# ESP8266_SENSOR_Sheet_1.net
KiCad netlist of a schematic drawn in Altium Designer
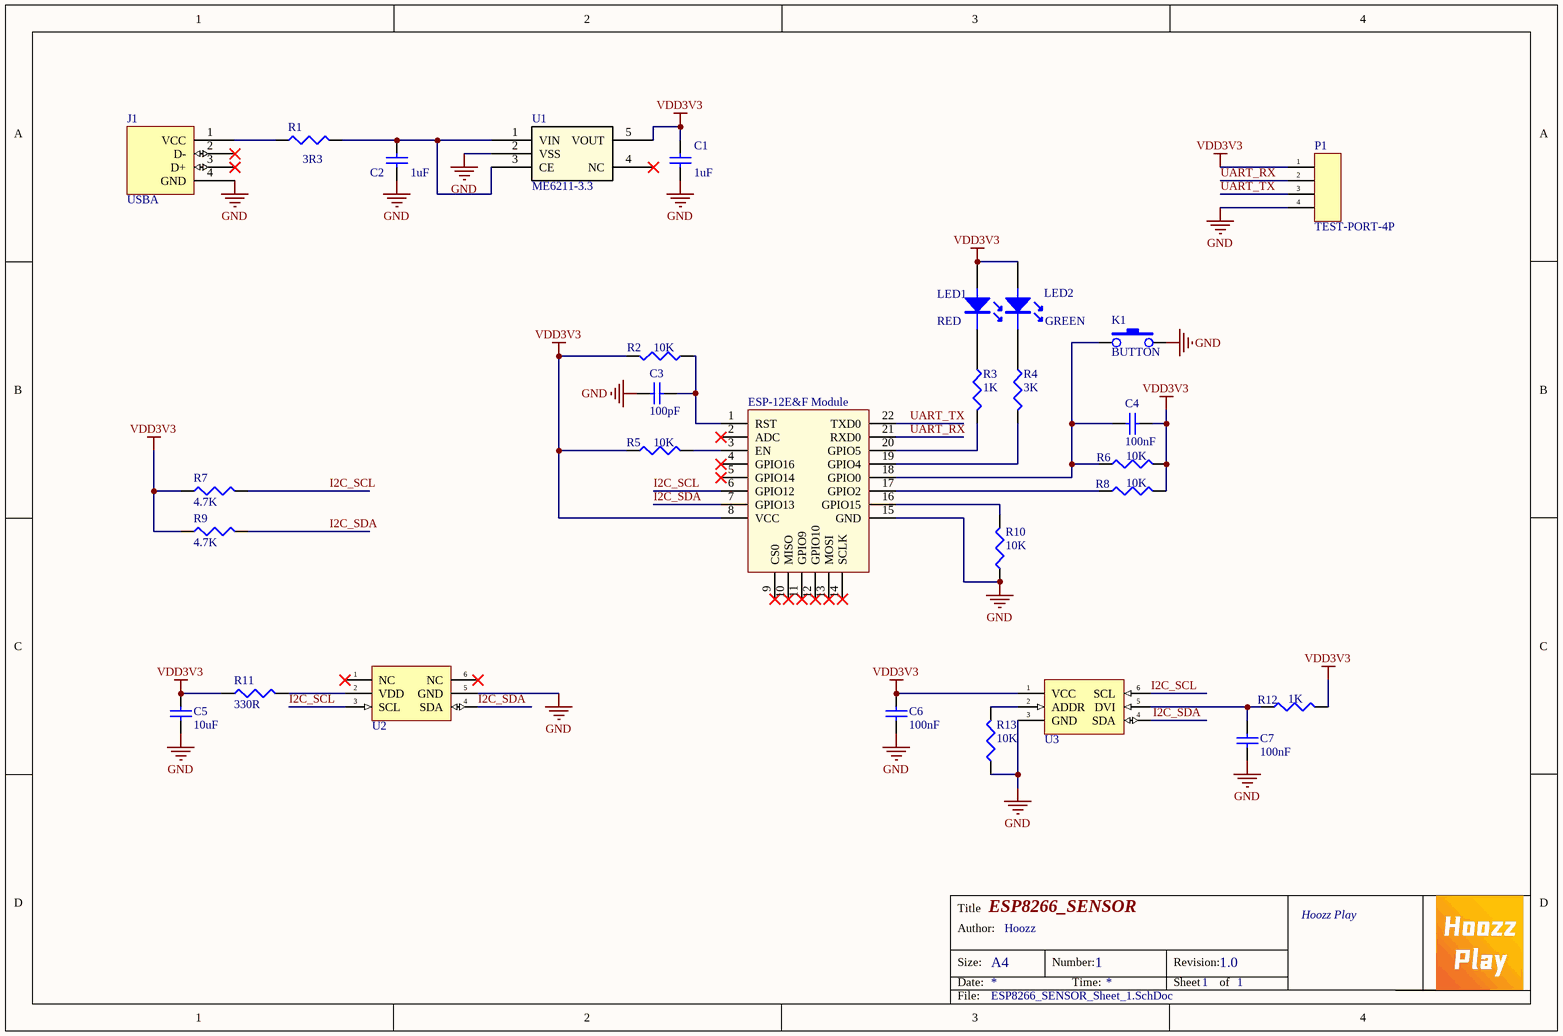
[diagram p0: ESP8266_SENSOR_Sheet_1.SchDoc]

(export (version "E")
  (design (tool "Eeschema 10.0.6"))
  (components
    (comp (ref "C1")
      (value "1uF")
      (footprint "0603")
      (description "Capacitor")
      (fields (field (name "Comment") "Cap") (field (name "PUBLISHER") "Altium Limited"))
      (libsource (lib "CORE_COMPONENT") (part "Cap"))
    )
    (comp (ref "C2")
      (value "1uF")
      (footprint "0603")
      (description "Capacitor")
      (fields (field (name "Comment") "Cap") (field (name "PUBLISHER") "Altium Limited"))
      (libsource (lib "CORE_COMPONENT") (part "Cap"))
    )
    (comp (ref "C3")
      (value "100pF")
      (footprint "0603")
      (description "Capacitor")
      (fields (field (name "Comment") "Cap") (field (name "PUBLISHER") "Altium Limited"))
      (libsource (lib "CORE_COMPONENT") (part "Cap"))
    )
    (comp (ref "C4")
      (value "100nF")
      (footprint "0603")
      (description "Capacitor")
      (fields (field (name "Comment") "Cap") (field (name "PUBLISHER") "Altium Limited"))
      (libsource (lib "CORE_COMPONENT") (part "Cap"))
    )
    (comp (ref "C5")
      (value "10uF")
      (footprint "0603")
      (description "Capacitor")
      (fields (field (name "Comment") "Cap") (field (name "PUBLISHER") "Altium Limited"))
      (libsource (lib "CORE_COMPONENT") (part "Cap"))
    )
    (comp (ref "C6")
      (value "100nF")
      (footprint "0603")
      (description "Capacitor")
      (fields (field (name "Comment") "Cap") (field (name "PUBLISHER") "Altium Limited"))
      (libsource (lib "CORE_COMPONENT") (part "Cap"))
    )
    (comp (ref "C7")
      (value "100nF")
      (footprint "0603")
      (description "Capacitor")
      (fields (field (name "Comment") "Cap") (field (name "PUBLISHER") "Altium Limited"))
      (libsource (lib "CORE_COMPONENT") (part "Cap"))
    )
    (comp (ref "J1")
      (value "USBA")
      (footprint "USB-A-2")
      (description "USB2.0")
      (libsource (lib "CORE_COMPONENT") (part "USBA"))
    )
    (comp (ref "K1") (value "BUTTON") (footprint "BUTTON") (libsource (lib "CORE_COMPONENT") (part "BUTTON")))
    (comp (ref "LED1") (value "RED") (footprint "LED0603") (libsource (lib "CORE_COMPONENT") (part "LED")))
    (comp (ref "LED2") (value "GREEN") (footprint "LED0603") (libsource (lib "CORE_COMPONENT") (part "LED")))
    (comp (ref "M1")
      (value "ESP-12E&F Module")
      (footprint "ESP-12E&F Module")
      (libsource (lib "CORE_COMPONENT") (part "ESP-12E&F Module"))
    )
    (comp (ref "P1")
      (value "TEST-PORT-4P")
      (footprint "TEST_PORT_4P")
      (libsource (lib "CORE_COMPONENT") (part "TEST-PORT-4P"))
    )
    (comp (ref "R1")
      (value "3R3")
      (footprint "0603")
      (description "Resistor")
      (fields (field (name "Comment") "Res") (field (name "PUBLISHER") "Altium Limited"))
      (libsource (lib "CORE_COMPONENT") (part "Res"))
    )
    (comp (ref "R2")
      (value "10K")
      (footprint "0603")
      (description "Resistor")
      (fields (field (name "Comment") "Res") (field (name "PUBLISHER") "Altium Limited"))
      (libsource (lib "CORE_COMPONENT") (part "Res"))
    )
    (comp (ref "R3")
      (value "1K")
      (footprint "0603")
      (description "Resistor")
      (fields (field (name "Comment") "Res") (field (name "PUBLISHER") "Altium Limited"))
      (libsource (lib "CORE_COMPONENT") (part "Res"))
    )
    (comp (ref "R4")
      (value "3K")
      (footprint "0603")
      (description "Resistor")
      (fields (field (name "Comment") "Res") (field (name "PUBLISHER") "Altium Limited"))
      (libsource (lib "CORE_COMPONENT") (part "Res"))
    )
    (comp (ref "R5")
      (value "10K")
      (footprint "0603")
      (description "Resistor")
      (fields (field (name "Comment") "Res") (field (name "PUBLISHER") "Altium Limited"))
      (libsource (lib "CORE_COMPONENT") (part "Res"))
    )
    (comp (ref "R6")
      (value "10K")
      (footprint "0603")
      (description "Resistor")
      (fields (field (name "Comment") "Res") (field (name "PUBLISHER") "Altium Limited"))
      (libsource (lib "CORE_COMPONENT") (part "Res"))
    )
    (comp (ref "R7")
      (value "4.7K")
      (footprint "0603")
      (description "Resistor")
      (fields (field (name "Comment") "Res") (field (name "PUBLISHER") "Altium Limited"))
      (libsource (lib "CORE_COMPONENT") (part "Res"))
    )
    (comp (ref "R8")
      (value "10K")
      (footprint "0603")
      (description "Resistor")
      (fields (field (name "Comment") "Res") (field (name "PUBLISHER") "Altium Limited"))
      (libsource (lib "CORE_COMPONENT") (part "Res"))
    )
    (comp (ref "R9")
      (value "4.7K")
      (footprint "0603")
      (description "Resistor")
      (fields (field (name "Comment") "Res") (field (name "PUBLISHER") "Altium Limited"))
      (libsource (lib "CORE_COMPONENT") (part "Res"))
    )
    (comp (ref "R10")
      (value "10K")
      (footprint "0603")
      (description "Resistor")
      (fields (field (name "Comment") "Res") (field (name "PUBLISHER") "Altium Limited"))
      (libsource (lib "CORE_COMPONENT") (part "Res"))
    )
    (comp (ref "R11")
      (value "330R")
      (footprint "0603")
      (description "Resistor")
      (fields (field (name "Comment") "Res") (field (name "PUBLISHER") "Altium Limited"))
      (libsource (lib "CORE_COMPONENT") (part "Res"))
    )
    (comp (ref "R12")
      (value "1K")
      (footprint "0603")
      (description "Resistor")
      (fields (field (name "Comment") "Res") (field (name "PUBLISHER") "Altium Limited"))
      (libsource (lib "CORE_COMPONENT") (part "Res"))
    )
    (comp (ref "R13")
      (value "10K")
      (footprint "0603")
      (description "Resistor")
      (fields (field (name "Comment") "Res") (field (name "PUBLISHER") "Altium Limited"))
      (libsource (lib "CORE_COMPONENT") (part "Res"))
    )
    (comp (ref "U1")
      (value "ME6211-3.3")
      (footprint "SOT-23-5")
      (description "No Description Available")
      (fields
        (field (name "MANUFACTURER") "Texas Instruments")
        (field (name "MANUFACTURER_PART_NUMBER") "REG102NA-2.5/250")
        (field (name "COPYRIGHT") "Copyright (C) 2018 Accelerated Designs. All rights reserved")
      )
      (libsource (lib "CORE_COMPONENT") (part "ME6211-3.3"))
    )
    (comp (ref "U2") (value "AHT20") (footprint "AHT20") (libsource (lib "CORE_COMPONENT") (part "AHT20")))
    (comp (ref "U3") (value "BH1750") (footprint "BH1750") (libsource (lib "CORE_COMPONENT") (part "BH1750")))
  )
  (nets
    (net (code "1") (name "/I2C_SCL") (class "Default")
      (node (ref "M1") (pin "6") (pinfunction "GPIO12_6") (pintype "passive"))
      (node (ref "R7") (pin "2") (pinfunction "2_2") (pintype "passive"))
      (node (ref "U2") (pin "3") (pinfunction "SCL_3") (pintype "input"))
      (node (ref "U3") (pin "6") (pinfunction "SCL_6") (pintype "input"))
    )
    (net (code "2") (name "/I2C_SDA") (class "Default")
      (node (ref "M1") (pin "7") (pinfunction "GPIO13_7") (pintype "passive"))
      (node (ref "R9") (pin "2") (pinfunction "2_2") (pintype "passive"))
      (node (ref "U2") (pin "4") (pinfunction "SDA_4") (pintype "bidirectional"))
      (node (ref "U3") (pin "4") (pinfunction "SDA_4") (pintype "bidirectional"))
    )
    (net (code "3") (name "/UART_RX") (class "Default")
      (node (ref "M1") (pin "21") (pinfunction "RXD0_21") (pintype "passive"))
      (node (ref "P1") (pin "2") (pintype "passive"))
    )
    (net (code "4") (name "/UART_TX") (class "Default")
      (node (ref "M1") (pin "22") (pinfunction "TXD0_22") (pintype "passive"))
      (node (ref "P1") (pin "3") (pintype "passive"))
    )
    (net (code "5") (name "GND") (class "Default")
      (node (ref "C1") (pin "1") (pinfunction "1_1") (pintype "passive"))
      (node (ref "C2") (pin "1") (pinfunction "1_1") (pintype "passive"))
      (node (ref "C3") (pin "2") (pinfunction "2_2") (pintype "passive"))
      (node (ref "C5") (pin "2") (pinfunction "2_2") (pintype "passive"))
      (node (ref "C6") (pin "2") (pinfunction "2_2") (pintype "passive"))
      (node (ref "C7") (pin "2") (pinfunction "2_2") (pintype "passive"))
      (node (ref "J1") (pin "4") (pinfunction "GND_4") (pintype "power_in"))
      (node (ref "K1") (pin "2") (pinfunction "2_2") (pintype "passive"))
      (node (ref "M1") (pin "15") (pinfunction "GND_15") (pintype "passive"))
      (node (ref "P1") (pin "4") (pintype "passive"))
      (node (ref "R10") (pin "1") (pinfunction "1_1") (pintype "passive"))
      (node (ref "R13") (pin "1") (pinfunction "1_1") (pintype "passive"))
      (node (ref "U1") (pin "2") (pinfunction "VSS_2") (pintype "power_in"))
      (node (ref "U2") (pin "5") (pinfunction "GND_5") (pintype "power_in"))
      (node (ref "U3") (pin "3") (pinfunction "GND_3") (pintype "power_in"))
    )
    (net (code "6") (name "Net-(J1-VCC)") (class "Default")
      (node (ref "J1") (pin "1") (pinfunction "VCC_1") (pintype "power_in"))
      (node (ref "R1") (pin "1") (pinfunction "1_1") (pintype "passive"))
    )
    (net (code "7") (name "Net-(LED1-K)") (class "Default")
      (node (ref "LED1") (pin "2") (pinfunction "K_2") (pintype "passive"))
      (node (ref "R3") (pin "1") (pinfunction "1_1") (pintype "passive"))
    )
    (net (code "8") (name "Net-(LED2-K)") (class "Default")
      (node (ref "LED2") (pin "2") (pinfunction "K_2") (pintype "passive"))
      (node (ref "R4") (pin "1") (pinfunction "1_1") (pintype "passive"))
    )
    (net (code "9") (name "Net-(M1-EN)") (class "Default")
      (node (ref "M1") (pin "3") (pinfunction "EN_3") (pintype "passive"))
      (node (ref "R5") (pin "2") (pinfunction "2_2") (pintype "passive"))
    )
    (net (code "10") (name "Net-(M1-GPIO0)") (class "Default")
      (node (ref "C4") (pin "2") (pinfunction "2_2") (pintype "passive"))
      (node (ref "K1") (pin "1") (pinfunction "1_1") (pintype "passive"))
      (node (ref "M1") (pin "18") (pinfunction "GPIO0_18") (pintype "passive"))
      (node (ref "R6") (pin "1") (pinfunction "1_1") (pintype "passive"))
    )
    (net (code "11") (name "Net-(M1-GPIO2)") (class "Default")
      (node (ref "M1") (pin "17") (pinfunction "GPIO2_17") (pintype "passive"))
      (node (ref "R8") (pin "1") (pinfunction "1_1") (pintype "passive"))
    )
    (net (code "12") (name "Net-(M1-GPIO4)") (class "Default")
      (node (ref "M1") (pin "19") (pinfunction "GPIO4_19") (pintype "passive"))
      (node (ref "R4") (pin "2") (pinfunction "2_2") (pintype "passive"))
    )
    (net (code "13") (name "Net-(M1-GPIO5)") (class "Default")
      (node (ref "M1") (pin "20") (pinfunction "GPIO5_20") (pintype "passive"))
      (node (ref "R3") (pin "2") (pinfunction "2_2") (pintype "passive"))
    )
    (net (code "14") (name "Net-(M1-GPIO15)") (class "Default")
      (node (ref "M1") (pin "16") (pinfunction "GPIO15_16") (pintype "passive"))
      (node (ref "R10") (pin "2") (pinfunction "2_2") (pintype "passive"))
    )
    (net (code "15") (name "Net-(M1-RST)") (class "Default")
      (node (ref "C3") (pin "1") (pinfunction "1_1") (pintype "passive"))
      (node (ref "M1") (pin "1") (pinfunction "RST_1") (pintype "passive"))
      (node (ref "R2") (pin "1") (pinfunction "1_1") (pintype "passive"))
    )
    (net (code "16") (name "Net-(U1-CE)") (class "Default")
      (node (ref "C2") (pin "2") (pinfunction "2_2") (pintype "passive"))
      (node (ref "R1") (pin "2") (pinfunction "2_2") (pintype "passive"))
      (node (ref "U1") (pin "1") (pinfunction "VIN_1") (pintype "power_in"))
      (node (ref "U1") (pin "3") (pinfunction "CE_3") (pintype "passive"))
    )
    (net (code "17") (name "Net-(U2-VDD)") (class "Default")
      (node (ref "R11") (pin "2") (pinfunction "2_2") (pintype "passive"))
      (node (ref "U2") (pin "2") (pinfunction "VDD_2") (pintype "power_in"))
    )
    (net (code "18") (name "Net-(U3-ADDR)") (class "Default")
      (node (ref "R13") (pin "2") (pinfunction "2_2") (pintype "passive"))
      (node (ref "U3") (pin "2") (pinfunction "ADDR_2") (pintype "input"))
    )
    (net (code "19") (name "Net-(U3-DVI)") (class "Default")
      (node (ref "C7") (pin "1") (pinfunction "1_1") (pintype "passive"))
      (node (ref "R12") (pin "1") (pinfunction "1_1") (pintype "passive"))
      (node (ref "U3") (pin "5") (pinfunction "DVI_5") (pintype "input"))
    )
    (net (code "20") (name "VDD3V3") (class "Default")
      (node (ref "C1") (pin "2") (pinfunction "2_2") (pintype "passive"))
      (node (ref "C4") (pin "1") (pinfunction "1_1") (pintype "passive"))
      (node (ref "C5") (pin "1") (pinfunction "1_1") (pintype "passive"))
      (node (ref "C6") (pin "1") (pinfunction "1_1") (pintype "passive"))
      (node (ref "LED1") (pin "1") (pinfunction "A_1") (pintype "passive"))
      (node (ref "LED2") (pin "1") (pinfunction "A_1") (pintype "passive"))
      (node (ref "M1") (pin "8") (pinfunction "VCC_8") (pintype "passive"))
      (node (ref "P1") (pin "1") (pintype "passive"))
      (node (ref "R11") (pin "1") (pinfunction "1_1") (pintype "passive"))
      (node (ref "R12") (pin "2") (pinfunction "2_2") (pintype "passive"))
      (node (ref "R2") (pin "2") (pinfunction "2_2") (pintype "passive"))
      (node (ref "R5") (pin "1") (pinfunction "1_1") (pintype "passive"))
      (node (ref "R6") (pin "2") (pinfunction "2_2") (pintype "passive"))
      (node (ref "R7") (pin "1") (pinfunction "1_1") (pintype "passive"))
      (node (ref "R8") (pin "2") (pinfunction "2_2") (pintype "passive"))
      (node (ref "R9") (pin "1") (pinfunction "1_1") (pintype "passive"))
      (node (ref "U1") (pin "5") (pinfunction "VOUT_5") (pintype "power_in"))
      (node (ref "U3") (pin "1") (pinfunction "VCC_1") (pintype "power_in"))
    )
    (net (code "21") (name "unconnected-(J1-D+-Pad3)") (class "Default")
      (node (ref "J1") (pin "3") (pinfunction "D+_3") (pintype "bidirectional+no_connect"))
    )
    (net (code "22") (name "unconnected-(J1-D--Pad2)") (class "Default")
      (node (ref "J1") (pin "2") (pinfunction "D-_2") (pintype "bidirectional+no_connect"))
    )
    (net (code "23") (name "unconnected-(M1-ADC-Pad2)") (class "Default")
      (node (ref "M1") (pin "2") (pinfunction "ADC_2") (pintype "passive+no_connect"))
    )
    (net (code "24") (name "unconnected-(M1-CS0-Pad9)") (class "Default")
      (node (ref "M1") (pin "9") (pinfunction "CS0_9") (pintype "passive+no_connect"))
    )
    (net (code "25") (name "unconnected-(M1-GPIO9-Pad11)") (class "Default")
      (node (ref "M1") (pin "11") (pinfunction "GPIO9_11") (pintype "passive+no_connect"))
    )
    (net (code "26") (name "unconnected-(M1-GPIO10-Pad12)") (class "Default")
      (node (ref "M1") (pin "12") (pinfunction "GPIO10_12") (pintype "passive+no_connect"))
    )
    (net (code "27") (name "unconnected-(M1-GPIO14-Pad5)") (class "Default")
      (node (ref "M1") (pin "5") (pinfunction "GPIO14_5") (pintype "passive+no_connect"))
    )
    (net (code "28") (name "unconnected-(M1-GPIO16-Pad4)") (class "Default")
      (node (ref "M1") (pin "4") (pinfunction "GPIO16_4") (pintype "passive+no_connect"))
    )
    (net (code "29") (name "unconnected-(M1-MISO-Pad10)") (class "Default")
      (node (ref "M1") (pin "10") (pinfunction "MISO_10") (pintype "passive+no_connect"))
    )
    (net (code "30") (name "unconnected-(M1-MOSI-Pad13)") (class "Default")
      (node (ref "M1") (pin "13") (pinfunction "MOSI_13") (pintype "passive+no_connect"))
    )
    (net (code "31") (name "unconnected-(M1-SCLK-Pad14)") (class "Default")
      (node (ref "M1") (pin "14") (pinfunction "SCLK_14") (pintype "passive+no_connect"))
    )
    (net (code "32") (name "unconnected-(U1-NC-Pad4)") (class "Default")
      (node (ref "U1") (pin "4") (pinfunction "NC_4") (pintype "passive+no_connect"))
    )
    (net (code "33") (name "unconnected-(U2-NC-Pad1)") (class "Default")
      (node (ref "U2") (pin "1") (pinfunction "NC_1") (pintype "tri_state+no_connect"))
    )
    (net (code "34") (name "unconnected-(U2-NC-Pad6)") (class "Default")
      (node (ref "U2") (pin "6") (pinfunction "NC_6") (pintype "tri_state+no_connect"))
    )
  )
)
